# Task3.net
KiCad netlist of a schematic drawn in EAGLE
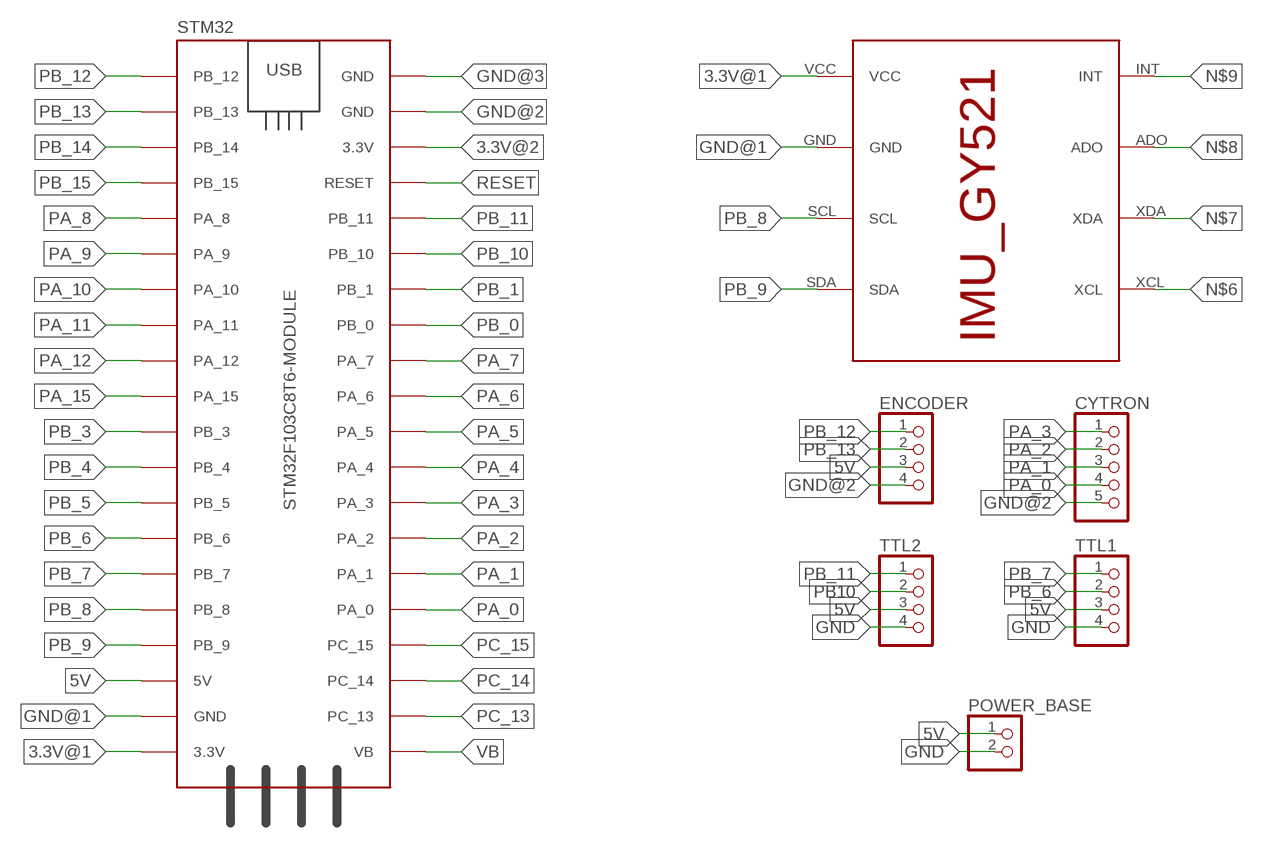
[diagram p0: schematic, sheet 1]

(export (version "E")
  (design (tool "Eeschema 10.0.6"))
  (components
    (comp (ref "CYTRON")
      (value "PINHD-5_DATA")
      (footprint "eagle-import:1X05_DATA")
      (libsource (lib "eagle-import") (part "PINHD-5_DATA"))
    )
    (comp (ref "ENCODER")
      (value "PINHD-4_DATA")
      (footprint "eagle-import:1X04_DATA")
      (libsource (lib "eagle-import") (part "PINHD-4_DATA"))
    )
    (comp (ref "POWER_BASE")
      (value "PINHD-2_DATA")
      (footprint "eagle-import:1X02_DATA")
      (libsource (lib "eagle-import") (part "PINHD-2_DATA"))
    )
    (comp (ref "STM32")
      (value "STM32F103C8T6-MODULE")
      (footprint "eagle-import:STM32F103C8T6-MODULE")
      (libsource (lib "eagle-import") (part "STM32F103C8T6-MODULE"))
    )
    (comp (ref "TTL1")
      (value "PINHD-4_DATA")
      (footprint "eagle-import:1X04_DATA")
      (libsource (lib "eagle-import") (part "PINHD-4_DATA"))
    )
    (comp (ref "TTL2")
      (value "PINHD-4_DATA")
      (footprint "eagle-import:1X04_DATA")
      (libsource (lib "eagle-import") (part "PINHD-4_DATA"))
    )
    (comp (ref "U$1")
      (value "IMU_ROBOCON_GY521")
      (footprint "eagle-import:IMU_GY521")
      (libsource (lib "eagle-import") (part "IMU_ROBOCON_GY521"))
    )
  )
  (nets
    (net (code "1") (name "3.3V@1") (class "Default")
      (node (ref "STM32") (pin "3.3V_1") (pinfunction "3.3V_3.3V_1") (pintype "bidirectional"))
      (node (ref "U$1") (pin "VCC") (pinfunction "VCC_VCC") (pintype "bidirectional"))
    )
    (net (code "2") (name "3.3V@2") (class "Default")
      (node (ref "STM32") (pin "3.3V_2") (pinfunction "3.3V_3.3V_2") (pintype "bidirectional"))
    )
    (net (code "3") (name "5V") (class "Default")
      (node (ref "ENCODER") (pin "3") (pinfunction "3_3") (pintype "passive"))
      (node (ref "POWER_BASE") (pin "1") (pinfunction "1_1") (pintype "passive"))
      (node (ref "STM32") (pin "5V") (pinfunction "5V_5V") (pintype "bidirectional"))
      (node (ref "TTL1") (pin "3") (pinfunction "3_3") (pintype "passive"))
      (node (ref "TTL2") (pin "3") (pinfunction "3_3") (pintype "passive"))
    )
    (net (code "4") (name "GND") (class "Default")
      (node (ref "POWER_BASE") (pin "2") (pinfunction "2_2") (pintype "passive"))
      (node (ref "TTL1") (pin "4") (pinfunction "4_4") (pintype "passive"))
      (node (ref "TTL2") (pin "4") (pinfunction "4_4") (pintype "passive"))
    )
    (net (code "5") (name "GND@1") (class "Default")
      (node (ref "STM32") (pin "GND_1") (pinfunction "GND_GND_1") (pintype "bidirectional"))
      (node (ref "U$1") (pin "GND") (pinfunction "GND_GND") (pintype "bidirectional"))
    )
    (net (code "6") (name "GND@2") (class "Default")
      (node (ref "CYTRON") (pin "5") (pinfunction "5_5") (pintype "passive"))
      (node (ref "ENCODER") (pin "4") (pinfunction "4_4") (pintype "passive"))
      (node (ref "STM32") (pin "GND_2") (pinfunction "GND_GND_2") (pintype "bidirectional"))
    )
    (net (code "7") (name "GND@3") (class "Default")
      (node (ref "STM32") (pin "GND_3") (pinfunction "GND_GND_3") (pintype "power_in"))
    )
    (net (code "8") (name "N$6") (class "Default")
      (node (ref "U$1") (pin "XCL") (pinfunction "XCL_XCL") (pintype "bidirectional"))
    )
    (net (code "9") (name "N$7") (class "Default")
      (node (ref "U$1") (pin "XDA") (pinfunction "XDA_XDA") (pintype "bidirectional"))
    )
    (net (code "10") (name "N$8") (class "Default")
      (node (ref "U$1") (pin "ADO") (pinfunction "ADO_ADO") (pintype "bidirectional"))
    )
    (net (code "11") (name "N$9") (class "Default")
      (node (ref "U$1") (pin "INT") (pinfunction "INT_INT") (pintype "bidirectional"))
    )
    (net (code "12") (name "PA_0") (class "Default")
      (node (ref "CYTRON") (pin "4") (pinfunction "4_4") (pintype "passive"))
      (node (ref "STM32") (pin "PA_0") (pinfunction "PA_0_PA_0") (pintype "bidirectional"))
    )
    (net (code "13") (name "PA_1") (class "Default")
      (node (ref "CYTRON") (pin "3") (pinfunction "3_3") (pintype "passive"))
      (node (ref "STM32") (pin "PA_1") (pinfunction "PA_1_PA_1") (pintype "bidirectional"))
    )
    (net (code "14") (name "PA_2") (class "Default")
      (node (ref "CYTRON") (pin "2") (pinfunction "2_2") (pintype "passive"))
      (node (ref "STM32") (pin "PA_2") (pinfunction "PA_2_PA_2") (pintype "bidirectional"))
    )
    (net (code "15") (name "PA_3") (class "Default")
      (node (ref "CYTRON") (pin "1") (pinfunction "1_1") (pintype "passive"))
      (node (ref "STM32") (pin "PA_3") (pinfunction "PA_3_PA_3") (pintype "bidirectional"))
    )
    (net (code "16") (name "PA_4") (class "Default")
      (node (ref "STM32") (pin "PA_4") (pinfunction "PA_4_PA_4") (pintype "bidirectional"))
    )
    (net (code "17") (name "PA_5") (class "Default")
      (node (ref "STM32") (pin "PA_5") (pinfunction "PA_5_PA_5") (pintype "bidirectional"))
    )
    (net (code "18") (name "PA_6") (class "Default")
      (node (ref "STM32") (pin "PA_6") (pinfunction "PA_6_PA_6") (pintype "bidirectional"))
    )
    (net (code "19") (name "PA_7") (class "Default")
      (node (ref "STM32") (pin "PA_7") (pinfunction "PA_7_PA_7") (pintype "bidirectional"))
    )
    (net (code "20") (name "PA_8") (class "Default")
      (node (ref "STM32") (pin "PA_8") (pinfunction "PA_8_PA_8") (pintype "bidirectional"))
    )
    (net (code "21") (name "PA_9") (class "Default")
      (node (ref "STM32") (pin "PA_9") (pinfunction "PA_9_PA_9") (pintype "bidirectional"))
    )
    (net (code "22") (name "PA_10") (class "Default")
      (node (ref "STM32") (pin "PA_10") (pinfunction "PA_10_PA_10") (pintype "bidirectional"))
    )
    (net (code "23") (name "PA_11") (class "Default")
      (node (ref "STM32") (pin "PA_11") (pinfunction "PA_11_PA_11") (pintype "bidirectional"))
    )
    (net (code "24") (name "PA_12") (class "Default")
      (node (ref "STM32") (pin "PA_12") (pinfunction "PA_12_PA_12") (pintype "bidirectional"))
    )
    (net (code "25") (name "PA_15") (class "Default")
      (node (ref "STM32") (pin "PA_15") (pinfunction "PA_15_PA_15") (pintype "bidirectional"))
    )
    (net (code "26") (name "PB10") (class "Default")
      (node (ref "TTL2") (pin "2") (pinfunction "2_2") (pintype "passive"))
    )
    (net (code "27") (name "PB_0") (class "Default")
      (node (ref "STM32") (pin "PB_0") (pinfunction "PB_0_PB_0") (pintype "bidirectional"))
    )
    (net (code "28") (name "PB_1") (class "Default")
      (node (ref "STM32") (pin "PB_1") (pinfunction "PB_1_PB_1") (pintype "bidirectional"))
    )
    (net (code "29") (name "PB_3") (class "Default")
      (node (ref "STM32") (pin "PB_3") (pinfunction "PB_3_PB_3") (pintype "bidirectional"))
    )
    (net (code "30") (name "PB_4") (class "Default")
      (node (ref "STM32") (pin "PB_4") (pinfunction "PB_4_PB_4") (pintype "bidirectional"))
    )
    (net (code "31") (name "PB_5") (class "Default")
      (node (ref "STM32") (pin "PB_5") (pinfunction "PB_5_PB_5") (pintype "bidirectional"))
    )
    (net (code "32") (name "PB_6") (class "Default")
      (node (ref "STM32") (pin "PB_6") (pinfunction "PB_6_PB_6") (pintype "bidirectional"))
      (node (ref "TTL1") (pin "2") (pinfunction "2_2") (pintype "passive"))
    )
    (net (code "33") (name "PB_7") (class "Default")
      (node (ref "STM32") (pin "PB_7") (pinfunction "PB_7_PB_7") (pintype "bidirectional"))
      (node (ref "TTL1") (pin "1") (pinfunction "1_1") (pintype "passive"))
    )
    (net (code "34") (name "PB_8") (class "Default")
      (node (ref "STM32") (pin "PB_8") (pinfunction "PB_8_PB_8") (pintype "bidirectional"))
      (node (ref "U$1") (pin "SCL") (pinfunction "SCL_SCL") (pintype "bidirectional"))
    )
    (net (code "35") (name "PB_9") (class "Default")
      (node (ref "STM32") (pin "PB_9") (pinfunction "PB_9_PB_9") (pintype "bidirectional"))
      (node (ref "U$1") (pin "SDA") (pinfunction "SDA_SDA") (pintype "bidirectional"))
    )
    (net (code "36") (name "PB_10") (class "Default")
      (node (ref "STM32") (pin "PB_10") (pinfunction "PB_10_PB_10") (pintype "bidirectional"))
    )
    (net (code "37") (name "PB_11") (class "Default")
      (node (ref "STM32") (pin "PB_11") (pinfunction "PB_11_PB_11") (pintype "bidirectional"))
      (node (ref "TTL2") (pin "1") (pinfunction "1_1") (pintype "passive"))
    )
    (net (code "38") (name "PB_12") (class "Default")
      (node (ref "ENCODER") (pin "1") (pinfunction "1_1") (pintype "passive"))
      (node (ref "STM32") (pin "PB_12") (pinfunction "PB_12_PB_12") (pintype "bidirectional"))
    )
    (net (code "39") (name "PB_13") (class "Default")
      (node (ref "ENCODER") (pin "2") (pinfunction "2_2") (pintype "passive"))
      (node (ref "STM32") (pin "PB_13") (pinfunction "PB_13_PB_13") (pintype "bidirectional"))
    )
    (net (code "40") (name "PB_14") (class "Default")
      (node (ref "STM32") (pin "PB_14") (pinfunction "PB_14_PB_14") (pintype "bidirectional"))
    )
    (net (code "41") (name "PB_15") (class "Default")
      (node (ref "STM32") (pin "PB_15") (pinfunction "PB_15_PB_15") (pintype "bidirectional"))
    )
    (net (code "42") (name "PC_13") (class "Default")
      (node (ref "STM32") (pin "PC_13") (pinfunction "PC_13_PC_13") (pintype "bidirectional"))
    )
    (net (code "43") (name "PC_14") (class "Default")
      (node (ref "STM32") (pin "PC_14") (pinfunction "PC_14_PC_14") (pintype "bidirectional"))
    )
    (net (code "44") (name "PC_15") (class "Default")
      (node (ref "STM32") (pin "PC_15") (pinfunction "PC_15_PC_15") (pintype "bidirectional"))
    )
    (net (code "45") (name "RESET") (class "Default")
      (node (ref "STM32") (pin "RESET") (pinfunction "RESET_RESET") (pintype "bidirectional"))
    )
    (net (code "46") (name "VB") (class "Default")
      (node (ref "STM32") (pin "VB") (pinfunction "VB_VB") (pintype "bidirectional"))
    )
  )
)
